# CurrentSensorAC758-50.net
KiCad netlist of a schematic drawn in EAGLE
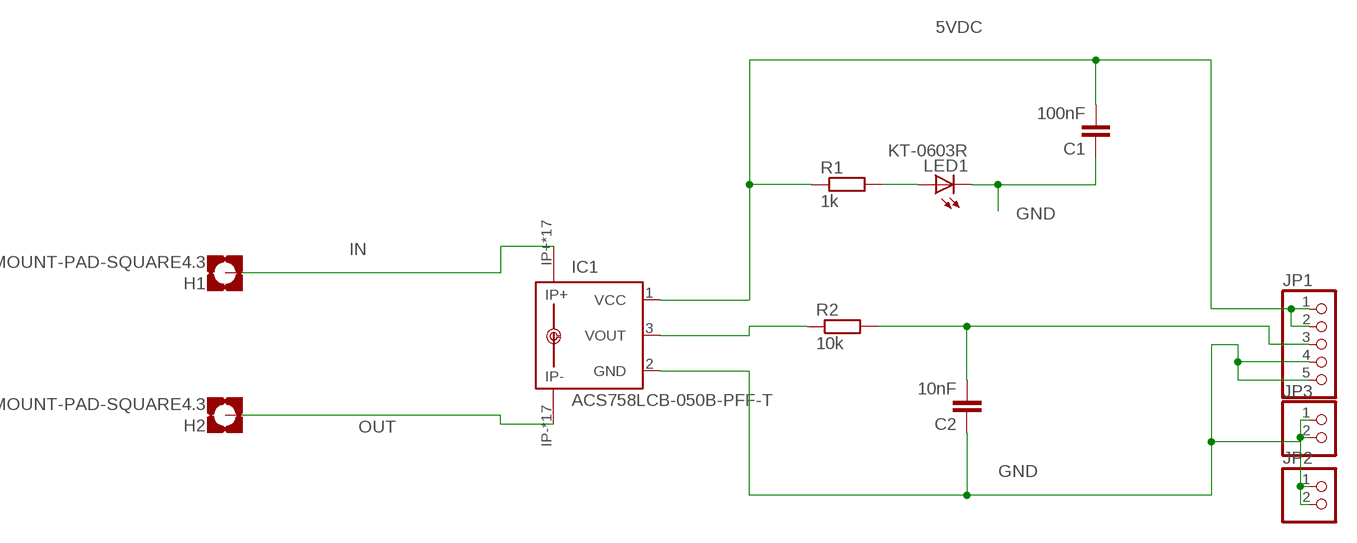
[diagram p0: schematic, sheet 1]

(export (version "E")
  (design (tool "Eeschema 10.0.6"))
  (components
    (comp (ref "C1")
      (value "100nF")
      (footprint "eagle-import:C0805")
      (libsource (lib "eagle-import") (part "C-EUC0805"))
    )
    (comp (ref "C2")
      (value "10nF")
      (footprint "eagle-import:C0805")
      (libsource (lib "eagle-import") (part "C-EUC0805"))
    )
    (comp (ref "H1")
      (value "MOUNT-PAD-SQUARE4.3")
      (footprint "eagle-import:4,3-PAD-SQUARE")
      (libsource (lib "eagle-import") (part "MOUNT-PAD-SQUARE4.3"))
    )
    (comp (ref "H2")
      (value "MOUNT-PAD-SQUARE4.3")
      (footprint "eagle-import:4,3-PAD-SQUARE")
      (libsource (lib "eagle-import") (part "MOUNT-PAD-SQUARE4.3"))
    )
    (comp (ref "IC1")
      (value "ACS758LCB-050B-PFF-T")
      (footprint "eagle-import:CB-PFF")
      (libsource (lib "eagle-import") (part "ACS758LCB-050B-PFF-T"))
    )
    (comp (ref "JP1")
      (value "PINHD-1X5")
      (footprint "eagle-import:1X05")
      (libsource (lib "eagle-import") (part "PINHD-1X5"))
    )
    (comp (ref "JP2")
      (value "PINHD-1X2")
      (footprint "eagle-import:1X02")
      (libsource (lib "eagle-import") (part "PINHD-1X2"))
    )
    (comp (ref "JP3")
      (value "PINHD-1X2")
      (footprint "eagle-import:1X02")
      (libsource (lib "eagle-import") (part "PINHD-1X2"))
    )
    (comp (ref "LED1")
      (value "KT-0603R")
      (footprint "eagle-import:CHIPLED_0603")
      (libsource (lib "eagle-import") (part "LEDCHIPLED_0603"))
    )
    (comp (ref "R1")
      (value "1k")
      (footprint "eagle-import:R0805")
      (libsource (lib "eagle-import") (part "R-EU_R0805"))
    )
    (comp (ref "R2")
      (value "10k")
      (footprint "eagle-import:R0805")
      (libsource (lib "eagle-import") (part "R-EU_R0805"))
    )
  )
  (nets
    (net (code "1") (name "/5VDC") (class "Default")
      (node (ref "C1") (pin "2") (pinfunction "2_2") (pintype "passive"))
      (node (ref "IC1") (pin "1") (pinfunction "VCC_1") (pintype "power_in"))
      (node (ref "JP1") (pin "1") (pinfunction "1_1") (pintype "passive"))
      (node (ref "JP1") (pin "2") (pinfunction "2_2") (pintype "passive"))
      (node (ref "R1") (pin "1") (pinfunction "1_1") (pintype "passive"))
    )
    (net (code "2") (name "/GND") (class "Default")
      (node (ref "C1") (pin "1") (pinfunction "1_1") (pintype "passive"))
      (node (ref "C2") (pin "1") (pinfunction "1_1") (pintype "passive"))
      (node (ref "IC1") (pin "2") (pinfunction "GND_2") (pintype "power_in"))
      (node (ref "JP1") (pin "4") (pinfunction "4_4") (pintype "passive"))
      (node (ref "JP1") (pin "5") (pinfunction "5_5") (pintype "passive"))
      (node (ref "JP2") (pin "1") (pinfunction "1_1") (pintype "passive"))
      (node (ref "JP2") (pin "2") (pinfunction "2_2") (pintype "passive"))
      (node (ref "JP3") (pin "1") (pinfunction "1_1") (pintype "passive"))
      (node (ref "JP3") (pin "2") (pinfunction "2_2") (pintype "passive"))
      (node (ref "LED1") (pin "C") (pinfunction "C_C") (pintype "passive"))
    )
    (net (code "3") (name "/IN") (class "Default")
      (node (ref "H1") (pin "B4,3") (pinfunction "MOUNT_B4,3") (pintype "passive"))
      (node (ref "IC1") (pin "IP+") (pinfunction "IP+_IP+") (pintype "passive"))
      (node (ref "IC1") (pin "IP+@10") (pinfunction "IP+_IP+@10") (pintype "passive"))
      (node (ref "IC1") (pin "IP+@11") (pinfunction "IP+_IP+@11") (pintype "passive"))
      (node (ref "IC1") (pin "IP+@12") (pinfunction "IP+_IP+@12") (pintype "passive"))
      (node (ref "IC1") (pin "IP+@13") (pinfunction "IP+_IP+@13") (pintype "passive"))
      (node (ref "IC1") (pin "IP+@14") (pinfunction "IP+_IP+@14") (pintype "passive"))
      (node (ref "IC1") (pin "IP+@15") (pinfunction "IP+_IP+@15") (pintype "passive"))
      (node (ref "IC1") (pin "IP+@16") (pinfunction "IP+_IP+@16") (pintype "passive"))
      (node (ref "IC1") (pin "IP+@17") (pinfunction "IP+_IP+@17") (pintype "passive"))
      (node (ref "IC1") (pin "IP+@2") (pinfunction "IP+_IP+@2") (pintype "passive"))
      (node (ref "IC1") (pin "IP+@3") (pinfunction "IP+_IP+@3") (pintype "passive"))
      (node (ref "IC1") (pin "IP+@4") (pinfunction "IP+_IP+@4") (pintype "passive"))
      (node (ref "IC1") (pin "IP+@5") (pinfunction "IP+_IP+@5") (pintype "passive"))
      (node (ref "IC1") (pin "IP+@6") (pinfunction "IP+_IP+@6") (pintype "passive"))
      (node (ref "IC1") (pin "IP+@7") (pinfunction "IP+_IP+@7") (pintype "passive"))
      (node (ref "IC1") (pin "IP+@8") (pinfunction "IP+_IP+@8") (pintype "passive"))
      (node (ref "IC1") (pin "IP+@9") (pinfunction "IP+_IP+@9") (pintype "passive"))
    )
    (net (code "4") (name "/OUT") (class "Default")
      (node (ref "H2") (pin "B4,3") (pinfunction "MOUNT_B4,3") (pintype "passive"))
      (node (ref "IC1") (pin "IP-") (pinfunction "IP-_IP-") (pintype "passive"))
      (node (ref "IC1") (pin "IP-@10") (pinfunction "IP-_IP-@10") (pintype "passive"))
      (node (ref "IC1") (pin "IP-@11") (pinfunction "IP-_IP-@11") (pintype "passive"))
      (node (ref "IC1") (pin "IP-@12") (pinfunction "IP-_IP-@12") (pintype "passive"))
      (node (ref "IC1") (pin "IP-@13") (pinfunction "IP-_IP-@13") (pintype "passive"))
      (node (ref "IC1") (pin "IP-@14") (pinfunction "IP-_IP-@14") (pintype "passive"))
      (node (ref "IC1") (pin "IP-@15") (pinfunction "IP-_IP-@15") (pintype "passive"))
      (node (ref "IC1") (pin "IP-@16") (pinfunction "IP-_IP-@16") (pintype "passive"))
      (node (ref "IC1") (pin "IP-@17") (pinfunction "IP-_IP-@17") (pintype "passive"))
      (node (ref "IC1") (pin "IP-@2") (pinfunction "IP-_IP-@2") (pintype "passive"))
      (node (ref "IC1") (pin "IP-@3") (pinfunction "IP-_IP-@3") (pintype "passive"))
      (node (ref "IC1") (pin "IP-@4") (pinfunction "IP-_IP-@4") (pintype "passive"))
      (node (ref "IC1") (pin "IP-@5") (pinfunction "IP-_IP-@5") (pintype "passive"))
      (node (ref "IC1") (pin "IP-@6") (pinfunction "IP-_IP-@6") (pintype "passive"))
      (node (ref "IC1") (pin "IP-@7") (pinfunction "IP-_IP-@7") (pintype "passive"))
      (node (ref "IC1") (pin "IP-@8") (pinfunction "IP-_IP-@8") (pintype "passive"))
      (node (ref "IC1") (pin "IP-@9") (pinfunction "IP-_IP-@9") (pintype "passive"))
    )
    (net (code "5") (name "Net-(C2-Pad2)") (class "Default")
      (node (ref "C2") (pin "2") (pinfunction "2_2") (pintype "passive"))
      (node (ref "JP1") (pin "3") (pinfunction "3_3") (pintype "passive"))
      (node (ref "R2") (pin "2") (pinfunction "2_2") (pintype "passive"))
    )
    (net (code "6") (name "Net-(IC1-VOUT)") (class "Default")
      (node (ref "IC1") (pin "3") (pinfunction "VOUT_3") (pintype "output"))
      (node (ref "R2") (pin "1") (pinfunction "1_1") (pintype "passive"))
    )
    (net (code "7") (name "Net-(LED1-PadA)") (class "Default")
      (node (ref "LED1") (pin "A") (pinfunction "A_A") (pintype "passive"))
      (node (ref "R1") (pin "2") (pinfunction "2_2") (pintype "passive"))
    )
  )
)
